# 25062016wearable_v1_1_-_Kopie.net
KiCad netlist of a schematic drawn in EAGLE
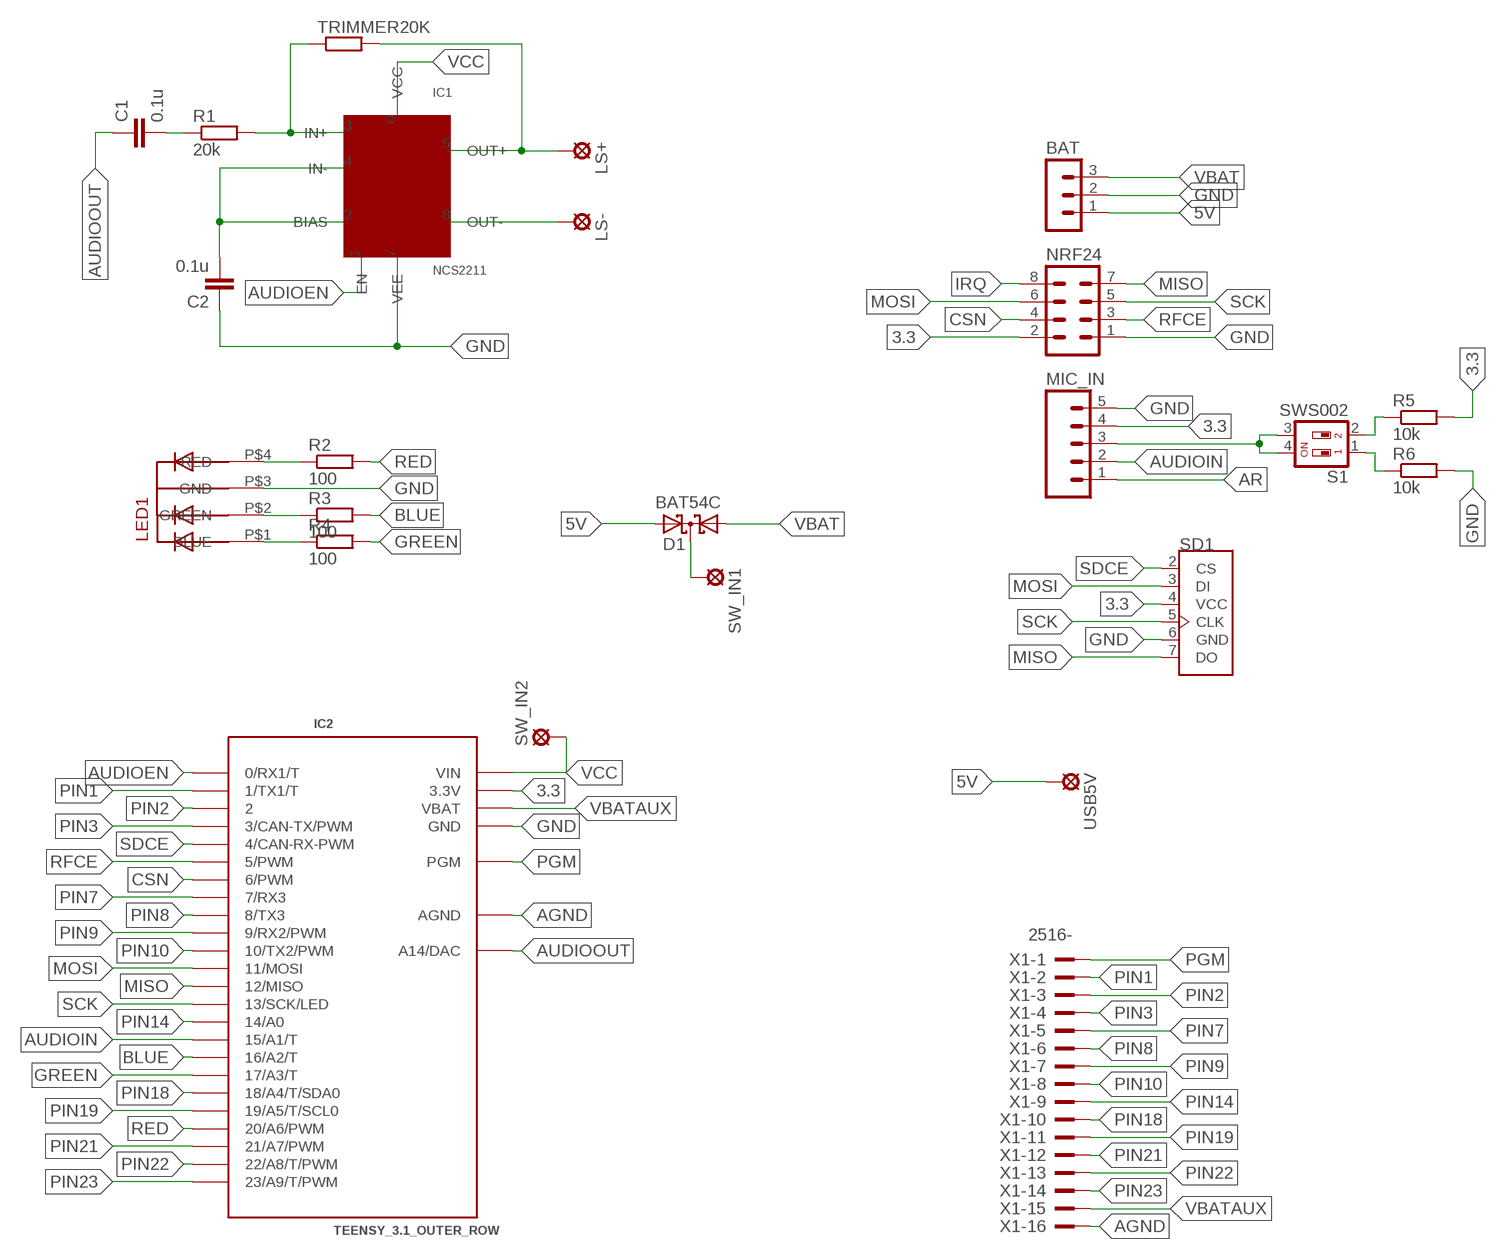
[diagram p0: schematic, sheet 1]

(export (version "E")
  (design (tool "Eeschema 10.0.6"))
  (components
    (comp (ref "BAT")
      (value "MA03-1")
      (footprint "eagle-import:MA03-1")
      (libsource (lib "eagle-import") (part "MA03-1"))
    )
    (comp (ref "C1")
      (value "0.1u")
      (footprint "eagle-import:C2.5-2")
      (libsource (lib "eagle-import") (part "C2.5/2"))
    )
    (comp (ref "C2")
      (value "0.1u")
      (footprint "eagle-import:C2.5-2")
      (libsource (lib "eagle-import") (part "C2.5/2"))
    )
    (comp (ref "D1")
      (value "BAT54C")
      (footprint "eagle-import:SOT23")
      (libsource (lib "eagle-import") (part "BAT54C"))
    )
    (comp (ref "IC1")
      (value "NCS2211")
      (footprint "eagle-import:SOIC-8")
      (libsource (lib "eagle-import") (part "NCS2211"))
    )
    (comp (ref "IC2")
      (value "TEENSY_3.1_OUTER_ROW")
      (footprint "eagle-import:TEENSY3-OUTER_ROW")
      (libsource (lib "eagle-import") (part "TEENSY_3.1_OUTER_ROW"))
    )
    (comp (ref "LED1")
      (value "5MMRGBLED")
      (footprint "eagle-import:LED5MMRGB")
      (libsource (lib "eagle-import") (part "5MMRGBLED"))
    )
    (comp (ref "LS+")
      (value "LSP10")
      (footprint "eagle-import:LSP10")
      (libsource (lib "eagle-import") (part "LSP10"))
    )
    (comp (ref "LS-")
      (value "LSP10")
      (footprint "eagle-import:LSP10")
      (libsource (lib "eagle-import") (part "LSP10"))
    )
    (comp (ref "MIC_IN")
      (value "MA05")
      (footprint "eagle-import:05PA")
      (libsource (lib "eagle-import") (part "MA05"))
    )
    (comp (ref "NRF24")
      (value "MA04-2")
      (footprint "eagle-import:MA04-2")
      (libsource (lib "eagle-import") (part "MA04-2"))
    )
    (comp (ref "R1")
      (value "20k")
      (footprint "eagle-import:0204_7")
      (libsource (lib "eagle-import") (part "R-EU_0204/7"))
    )
    (comp (ref "R2")
      (value "100")
      (footprint "eagle-import:0207_2V")
      (libsource (lib "eagle-import") (part "R-EU_0207/2V"))
    )
    (comp (ref "R3")
      (value "100")
      (footprint "eagle-import:0207_2V")
      (libsource (lib "eagle-import") (part "R-EU_0207/2V"))
    )
    (comp (ref "R4")
      (value "100")
      (footprint "eagle-import:0207_2V")
      (libsource (lib "eagle-import") (part "R-EU_0207/2V"))
    )
    (comp (ref "R5")
      (value "10k")
      (footprint "eagle-import:0207_2V")
      (libsource (lib "eagle-import") (part "R-EU_0207/2V"))
    )
    (comp (ref "R6")
      (value "10k")
      (footprint "eagle-import:0207_2V")
      (libsource (lib "eagle-import") (part "R-EU_0207/2V"))
    )
    (comp (ref "S1")
      (value "SWS002")
      (footprint "eagle-import:SMS-002")
      (libsource (lib "eagle-import") (part "SWS002"))
    )
    (comp (ref "SD1")
      (value "MICROSD_SF-MICROSD")
      (footprint "eagle-import:MICROSD_MICROSD")
      (libsource (lib "eagle-import") (part "MICROSD_SF-MICROSD"))
    )
    (comp (ref "SW_IN1")
      (value "SE11")
      (footprint "eagle-import:SE11")
      (libsource (lib "eagle-import") (part "SE11"))
    )
    (comp (ref "SW_IN2")
      (value "SE11")
      (footprint "eagle-import:SE11")
      (libsource (lib "eagle-import") (part "SE11"))
    )
    (comp (ref "TRIMMER20K")
      (value "R-EU_0207/2V")
      (footprint "eagle-import:0207_2V")
      (libsource (lib "eagle-import") (part "R-EU_0207/2V"))
    )
    (comp (ref "USB5V")
      (value "LSP10")
      (footprint "eagle-import:LSP10")
      (libsource (lib "eagle-import") (part "LSP10"))
    )
    (comp (ref "X1")
      (value "2516-")
      (footprint "eagle-import:PAK100_2500-16")
      (libsource (lib "eagle-import") (part "2516-"))
    )
  )
  (nets
    (net (code "1") (name "3.3") (class "Default")
      (node (ref "IC2") (pin "3.3V") (pinfunction "3.3V_3.3V") (pintype "power_in"))
      (node (ref "IC2") (pin "3.3V1") (pinfunction "3.3V_3.3V1") (pintype "power_in"))
      (node (ref "MIC_IN") (pin "4") (pinfunction "4_4") (pintype "passive"))
      (node (ref "NRF24") (pin "2") (pinfunction "2_2") (pintype "passive"))
      (node (ref "R5") (pin "2") (pinfunction "2_2") (pintype "passive"))
      (node (ref "SD1") (pin "4") (pinfunction "VCC_4") (pintype "power_in"))
    )
    (net (code "2") (name "5V") (class "Default")
      (node (ref "BAT") (pin "1") (pinfunction "1_1") (pintype "passive"))
      (node (ref "D1") (pin "2") (pinfunction "A2_2") (pintype "passive"))
      (node (ref "USB5V") (pin "MP") (pinfunction "MP_MP") (pintype "passive"))
    )
    (net (code "3") (name "AGND") (class "Default")
      (node (ref "IC2") (pin "AGND") (pinfunction "AGND_AGND") (pintype "power_in"))
      (node (ref "X1") (pin "16") (pinfunction "KL_16") (pintype "passive"))
    )
    (net (code "4") (name "AR") (class "Default")
      (node (ref "MIC_IN") (pin "1") (pinfunction "1_1") (pintype "passive"))
    )
    (net (code "5") (name "AUDIOEN") (class "Default")
      (node (ref "IC1") (pin "1") (pinfunction "EN_1") (pintype "bidirectional"))
      (node (ref "IC2") (pin "0") (pinfunction "0/RX1/T_0") (pintype "bidirectional"))
    )
    (net (code "6") (name "AUDIOIN") (class "Default")
      (node (ref "IC2") (pin "15/A1") (pinfunction "15/A1/T_15/A1") (pintype "bidirectional"))
      (node (ref "MIC_IN") (pin "2") (pinfunction "2_2") (pintype "passive"))
    )
    (net (code "7") (name "AUDIOOUT") (class "Default")
      (node (ref "C1") (pin "1") (pinfunction "1_1") (pintype "passive"))
      (node (ref "IC2") (pin "RESET/DAC") (pinfunction "A14/DAC_RESET/DAC") (pintype "bidirectional"))
    )
    (net (code "8") (name "BLUE") (class "Default")
      (node (ref "IC2") (pin "16/A2") (pinfunction "16/A2/T_16/A2") (pintype "bidirectional"))
      (node (ref "R3") (pin "2") (pinfunction "2_2") (pintype "passive"))
    )
    (net (code "9") (name "CSN") (class "Default")
      (node (ref "IC2") (pin "6") (pinfunction "6/PWM_6") (pintype "bidirectional"))
      (node (ref "NRF24") (pin "4") (pinfunction "4_4") (pintype "passive"))
    )
    (net (code "10") (name "GND") (class "Default")
      (node (ref "BAT") (pin "2") (pinfunction "2_2") (pintype "passive"))
      (node (ref "C2") (pin "1") (pinfunction "1_1") (pintype "passive"))
      (node (ref "IC1") (pin "7") (pinfunction "VEE_7") (pintype "bidirectional"))
      (node (ref "IC2") (pin "GND") (pinfunction "GND_GND") (pintype "power_in"))
      (node (ref "IC2") (pin "GND1") (pinfunction "GND_GND1") (pintype "power_in"))
      (node (ref "LED1") (pin "P$3") (pinfunction "GND_P$3") (pintype "bidirectional"))
      (node (ref "MIC_IN") (pin "5") (pinfunction "5_5") (pintype "passive"))
      (node (ref "NRF24") (pin "1") (pinfunction "1_1") (pintype "passive"))
      (node (ref "R6") (pin "2") (pinfunction "2_2") (pintype "passive"))
      (node (ref "SD1") (pin "6") (pinfunction "GND_6") (pintype "power_in"))
    )
    (net (code "11") (name "GREEN") (class "Default")
      (node (ref "IC2") (pin "17/A3") (pinfunction "17/A3/T_17/A3") (pintype "bidirectional"))
      (node (ref "R4") (pin "2") (pinfunction "2_2") (pintype "passive"))
    )
    (net (code "12") (name "IRQ") (class "Default")
      (node (ref "NRF24") (pin "8") (pinfunction "8_8") (pintype "passive"))
    )
    (net (code "13") (name "MISO") (class "Default")
      (node (ref "IC2") (pin "12") (pinfunction "12/MISO_12") (pintype "bidirectional"))
      (node (ref "NRF24") (pin "7") (pinfunction "7_7") (pintype "passive"))
      (node (ref "SD1") (pin "7") (pinfunction "DO_7") (pintype "output"))
    )
    (net (code "14") (name "MOSI") (class "Default")
      (node (ref "IC2") (pin "11") (pinfunction "11/MOSI_11") (pintype "bidirectional"))
      (node (ref "NRF24") (pin "6") (pinfunction "6_6") (pintype "passive"))
      (node (ref "SD1") (pin "3") (pinfunction "DI_3") (pintype "input"))
    )
    (net (code "15") (name "Net-(C1-Pad2)") (class "Default")
      (node (ref "C1") (pin "2") (pinfunction "2_2") (pintype "passive"))
      (node (ref "R1") (pin "1") (pinfunction "1_1") (pintype "passive"))
    )
    (net (code "16") (name "Net-(D1-CC)") (class "Default")
      (node (ref "D1") (pin "3") (pinfunction "CC_3") (pintype "passive"))
      (node (ref "SW_IN1") (pin "MP") (pinfunction "MP_MP") (pintype "passive"))
    )
    (net (code "17") (name "Net-(IC1-BIAS)") (class "Default")
      (node (ref "C2") (pin "2") (pinfunction "2_2") (pintype "passive"))
      (node (ref "IC1") (pin "2") (pinfunction "BIAS_2") (pintype "bidirectional"))
      (node (ref "IC1") (pin "4") (pinfunction "IN-_4") (pintype "bidirectional"))
    )
    (net (code "18") (name "Net-(IC1-IN+)") (class "Default")
      (node (ref "IC1") (pin "3") (pinfunction "IN+_3") (pintype "bidirectional"))
      (node (ref "R1") (pin "2") (pinfunction "2_2") (pintype "passive"))
      (node (ref "TRIMMER20K") (pin "1") (pinfunction "1_1") (pintype "passive"))
    )
    (net (code "19") (name "Net-(IC1-OUT+)") (class "Default")
      (node (ref "IC1") (pin "5") (pinfunction "OUT+_5") (pintype "bidirectional"))
      (node (ref "LS+") (pin "MP") (pinfunction "MP_MP") (pintype "passive"))
      (node (ref "TRIMMER20K") (pin "2") (pinfunction "2_2") (pintype "passive"))
    )
    (net (code "20") (name "Net-(IC1-OUT-)") (class "Default")
      (node (ref "IC1") (pin "8") (pinfunction "OUT-_8") (pintype "bidirectional"))
      (node (ref "LS-") (pin "MP") (pinfunction "MP_MP") (pintype "passive"))
    )
    (net (code "21") (name "Net-(LED1-BLUE)") (class "Default")
      (node (ref "LED1") (pin "P$1") (pinfunction "BLUE_P$1") (pintype "bidirectional"))
      (node (ref "R4") (pin "1") (pinfunction "1_1") (pintype "passive"))
    )
    (net (code "22") (name "Net-(LED1-GREEN)") (class "Default")
      (node (ref "LED1") (pin "P$2") (pinfunction "GREEN_P$2") (pintype "bidirectional"))
      (node (ref "R3") (pin "1") (pinfunction "1_1") (pintype "passive"))
    )
    (net (code "23") (name "Net-(LED1-RED)") (class "Default")
      (node (ref "LED1") (pin "P$4") (pinfunction "RED_P$4") (pintype "bidirectional"))
      (node (ref "R2") (pin "1") (pinfunction "1_1") (pintype "passive"))
    )
    (net (code "24") (name "Net-(MIC_IN-Pad3)") (class "Default")
      (node (ref "MIC_IN") (pin "3") (pinfunction "3_3") (pintype "passive"))
      (node (ref "S1") (pin "3") (pinfunction "3_3") (pintype "passive"))
      (node (ref "S1") (pin "4") (pinfunction "4_4") (pintype "passive"))
    )
    (net (code "25") (name "Net-(R5-Pad1)") (class "Default")
      (node (ref "R5") (pin "1") (pinfunction "1_1") (pintype "passive"))
      (node (ref "S1") (pin "2") (pinfunction "2_2") (pintype "passive"))
    )
    (net (code "26") (name "Net-(R6-Pad1)") (class "Default")
      (node (ref "R6") (pin "1") (pinfunction "1_1") (pintype "passive"))
      (node (ref "S1") (pin "1") (pinfunction "1_1") (pintype "passive"))
    )
    (net (code "27") (name "PGM") (class "Default")
      (node (ref "IC2") (pin "PGM") (pinfunction "PGM_PGM") (pintype "bidirectional"))
      (node (ref "X1") (pin "1") (pinfunction "KL_1") (pintype "passive"))
    )
    (net (code "28") (name "PIN1") (class "Default")
      (node (ref "IC2") (pin "1") (pinfunction "1/TX1/T_1") (pintype "bidirectional"))
      (node (ref "X1") (pin "2") (pinfunction "KL_2") (pintype "passive"))
    )
    (net (code "29") (name "PIN2") (class "Default")
      (node (ref "IC2") (pin "2") (pinfunction "2_2") (pintype "bidirectional"))
      (node (ref "X1") (pin "3") (pinfunction "KL_3") (pintype "passive"))
    )
    (net (code "30") (name "PIN3") (class "Default")
      (node (ref "IC2") (pin "3") (pinfunction "3/CAN-TX/PWM_3") (pintype "bidirectional"))
      (node (ref "X1") (pin "4") (pinfunction "KL_4") (pintype "passive"))
    )
    (net (code "31") (name "PIN7") (class "Default")
      (node (ref "IC2") (pin "7") (pinfunction "7/RX3_7") (pintype "bidirectional"))
      (node (ref "X1") (pin "5") (pinfunction "KL_5") (pintype "passive"))
    )
    (net (code "32") (name "PIN8") (class "Default")
      (node (ref "IC2") (pin "8") (pinfunction "8/TX3_8") (pintype "bidirectional"))
      (node (ref "X1") (pin "6") (pinfunction "KL_6") (pintype "passive"))
    )
    (net (code "33") (name "PIN9") (class "Default")
      (node (ref "IC2") (pin "9") (pinfunction "9/RX2/PWM_9") (pintype "bidirectional"))
      (node (ref "X1") (pin "7") (pinfunction "KL_7") (pintype "passive"))
    )
    (net (code "34") (name "PIN10") (class "Default")
      (node (ref "IC2") (pin "10") (pinfunction "10/TX2/PWM_10") (pintype "bidirectional"))
      (node (ref "X1") (pin "8") (pinfunction "KL_8") (pintype "passive"))
    )
    (net (code "35") (name "PIN14") (class "Default")
      (node (ref "IC2") (pin "14/A0") (pinfunction "14/A0_14/A0") (pintype "bidirectional"))
      (node (ref "X1") (pin "9") (pinfunction "KL_9") (pintype "passive"))
    )
    (net (code "36") (name "PIN18") (class "Default")
      (node (ref "IC2") (pin "18/A4") (pinfunction "18/A4/T/SDA0_18/A4") (pintype "bidirectional"))
      (node (ref "X1") (pin "10") (pinfunction "KL_10") (pintype "passive"))
    )
    (net (code "37") (name "PIN19") (class "Default")
      (node (ref "IC2") (pin "19/A5") (pinfunction "19/A5/T/SCL0_19/A5") (pintype "bidirectional"))
      (node (ref "X1") (pin "11") (pinfunction "KL_11") (pintype "passive"))
    )
    (net (code "38") (name "PIN21") (class "Default")
      (node (ref "IC2") (pin "21/A7") (pinfunction "21/A7/PWM_21/A7") (pintype "bidirectional"))
      (node (ref "X1") (pin "12") (pinfunction "KL_12") (pintype "passive"))
    )
    (net (code "39") (name "PIN22") (class "Default")
      (node (ref "IC2") (pin "22/A8") (pinfunction "22/A8/T/PWM_22/A8") (pintype "bidirectional"))
      (node (ref "X1") (pin "13") (pinfunction "KL_13") (pintype "passive"))
    )
    (net (code "40") (name "PIN23") (class "Default")
      (node (ref "IC2") (pin "23/A9") (pinfunction "23/A9/T/PWM_23/A9") (pintype "bidirectional"))
      (node (ref "X1") (pin "14") (pinfunction "KL_14") (pintype "passive"))
    )
    (net (code "41") (name "RED") (class "Default")
      (node (ref "IC2") (pin "20/A6") (pinfunction "20/A6/PWM_20/A6") (pintype "bidirectional"))
      (node (ref "R2") (pin "2") (pinfunction "2_2") (pintype "passive"))
    )
    (net (code "42") (name "RFCE") (class "Default")
      (node (ref "IC2") (pin "5") (pinfunction "5/PWM_5") (pintype "bidirectional"))
      (node (ref "NRF24") (pin "3") (pinfunction "3_3") (pintype "passive"))
    )
    (net (code "43") (name "SCK") (class "Default")
      (node (ref "IC2") (pin "13") (pinfunction "13/SCK/LED_13") (pintype "bidirectional"))
      (node (ref "NRF24") (pin "5") (pinfunction "5_5") (pintype "passive"))
      (node (ref "SD1") (pin "5") (pinfunction "CLK_5") (pintype "input"))
    )
    (net (code "44") (name "SDCE") (class "Default")
      (node (ref "IC2") (pin "4") (pinfunction "4/CAN-RX-PWM_4") (pintype "bidirectional"))
      (node (ref "SD1") (pin "2") (pinfunction "CS_2") (pintype "input"))
    )
    (net (code "45") (name "VBAT") (class "Default")
      (node (ref "BAT") (pin "3") (pinfunction "3_3") (pintype "passive"))
      (node (ref "D1") (pin "1") (pinfunction "A1_1") (pintype "passive"))
    )
    (net (code "46") (name "VBATAUX") (class "Default")
      (node (ref "IC2") (pin "VBAT") (pinfunction "VBAT_VBAT") (pintype "power_in"))
      (node (ref "X1") (pin "15") (pinfunction "KL_15") (pintype "passive"))
    )
    (net (code "47") (name "VCC") (class "Default")
      (node (ref "IC1") (pin "6") (pinfunction "VCC_6") (pintype "bidirectional"))
      (node (ref "IC2") (pin "VIN") (pinfunction "VIN_VIN") (pintype "power_in"))
      (node (ref "SW_IN2") (pin "MP") (pinfunction "MP_MP") (pintype "passive"))
    )
  )
)
